# MN12832JC-TeensyLC.net
KiCad netlist of a schematic drawn in EAGLE
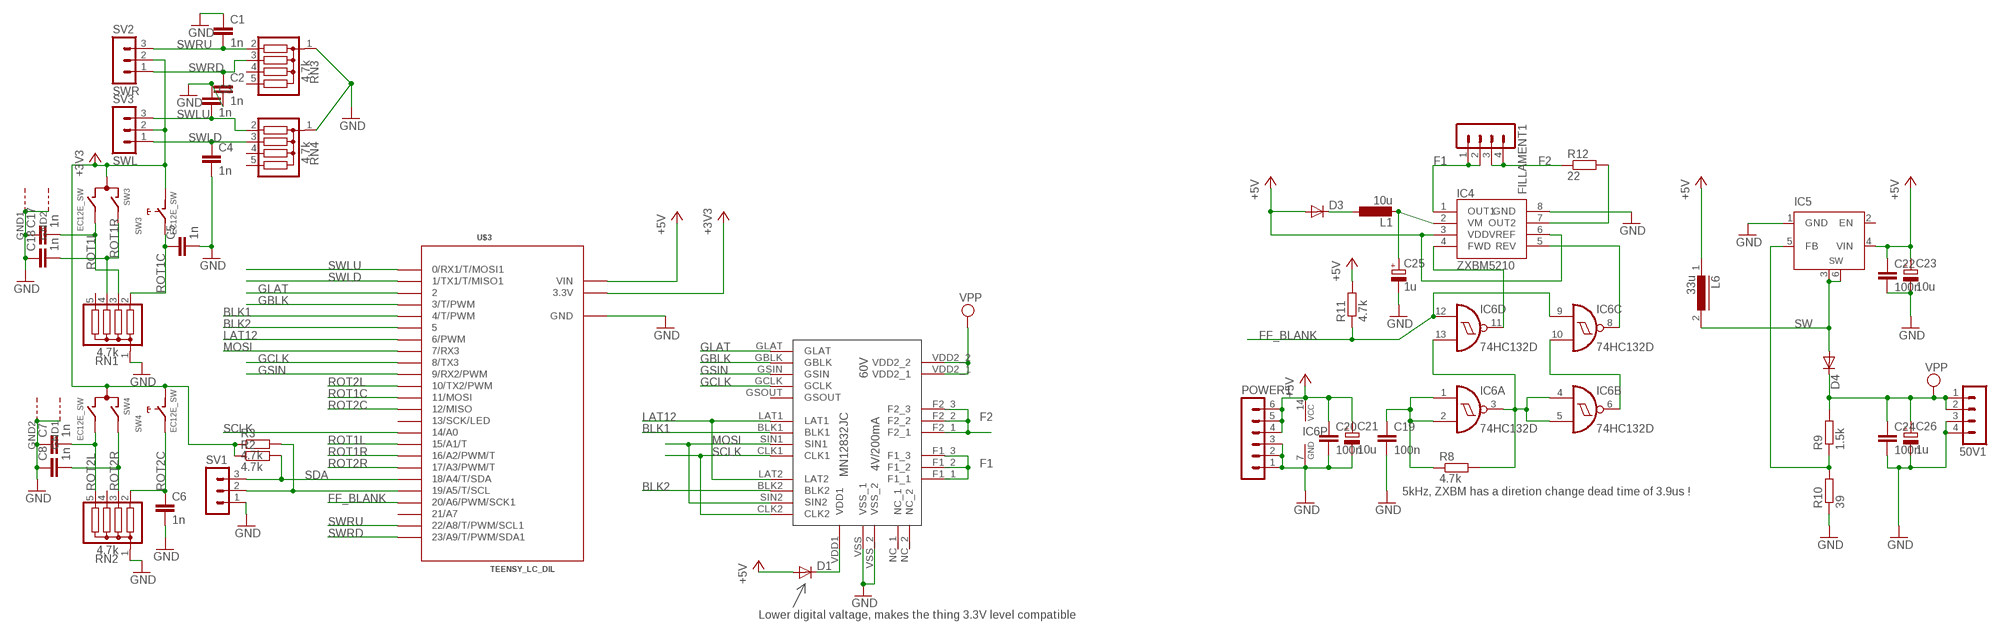
[diagram p0: schematic, sheet 1]

(export (version "E")
  (design (tool "Eeschema 10.0.6"))
  (components
    (comp (ref "50V1")
      (value "MA04-1")
      (footprint "eagle-import:MA04-1")
      (libsource (lib "eagle-import") (part "MA04-1"))
    )
    (comp (ref "C1")
      (value "1n")
      (footprint "eagle-import:C1206")
      (libsource (lib "eagle-import") (part "C-EUC1206"))
    )
    (comp (ref "C2")
      (value "1n")
      (footprint "eagle-import:C1206")
      (libsource (lib "eagle-import") (part "C-EUC1206"))
    )
    (comp (ref "C3")
      (value "1n")
      (footprint "eagle-import:C1206")
      (libsource (lib "eagle-import") (part "C-EUC1206"))
    )
    (comp (ref "C4")
      (value "1n")
      (footprint "eagle-import:C1206")
      (libsource (lib "eagle-import") (part "C-EUC1206"))
    )
    (comp (ref "C5")
      (value "1n")
      (footprint "eagle-import:C1206")
      (libsource (lib "eagle-import") (part "C-EUC1206"))
    )
    (comp (ref "C6")
      (value "1n")
      (footprint "eagle-import:C1206")
      (libsource (lib "eagle-import") (part "C-EUC1206"))
    )
    (comp (ref "C7")
      (value "1n")
      (footprint "eagle-import:C1206")
      (libsource (lib "eagle-import") (part "C-EUC1206"))
    )
    (comp (ref "C8")
      (value "1n")
      (footprint "eagle-import:C1206")
      (libsource (lib "eagle-import") (part "C-EUC1206"))
    )
    (comp (ref "C17")
      (value "1n")
      (footprint "eagle-import:C1206")
      (libsource (lib "eagle-import") (part "C-EUC1206"))
    )
    (comp (ref "C18")
      (value "1n")
      (footprint "eagle-import:C1206")
      (libsource (lib "eagle-import") (part "C-EUC1206"))
    )
    (comp (ref "C19")
      (value "100n")
      (footprint "eagle-import:C1206")
      (libsource (lib "eagle-import") (part "C-EUC1206"))
    )
    (comp (ref "C20")
      (value "100n")
      (footprint "eagle-import:C1206")
      (libsource (lib "eagle-import") (part "C-EUC1206"))
    )
    (comp (ref "C21")
      (value "10u")
      (footprint "eagle-import:153CLV-0807")
      (libsource (lib "eagle-import") (part "CPOL-EU153CLV-0807"))
    )
    (comp (ref "C22")
      (value "100n")
      (footprint "eagle-import:C1206")
      (libsource (lib "eagle-import") (part "C-EUC1206"))
    )
    (comp (ref "C23")
      (value "10u")
      (footprint "eagle-import:153CLV-0807")
      (libsource (lib "eagle-import") (part "CPOL-EU153CLV-0807"))
    )
    (comp (ref "C24")
      (value "100n")
      (footprint "eagle-import:C1206")
      (libsource (lib "eagle-import") (part "C-EUC1206"))
    )
    (comp (ref "C25")
      (value "1u")
      (footprint "eagle-import:153CLV-0505")
      (libsource (lib "eagle-import") (part "CPOL-EU153CLV-0505"))
    )
    (comp (ref "C26")
      (value "1u")
      (footprint "eagle-import:153CLV-0505")
      (libsource (lib "eagle-import") (part "CPOL-EU153CLV-0505"))
    )
    (comp (ref "D1")
      (value "DIODE-SMB")
      (footprint "eagle-import:SMB")
      (libsource (lib "eagle-import") (part "DIODE-SMB"))
    )
    (comp (ref "D3")
      (value "DIODE-SMB")
      (footprint "eagle-import:SMB")
      (libsource (lib "eagle-import") (part "DIODE-SMB"))
    )
    (comp (ref "D4")
      (value "DIODE-SMB")
      (footprint "eagle-import:SMB")
      (libsource (lib "eagle-import") (part "DIODE-SMB"))
    )
    (comp (ref "FILLAMENT1")
      (value "MA04-1")
      (footprint "eagle-import:MA04-1")
      (libsource (lib "eagle-import") (part "MA04-1"))
    )
    (comp (ref "IC4")
      (value "ZXBM5210")
      (footprint "eagle-import:SO8")
      (libsource (lib "eagle-import") (part "ZXBM5210"))
    )
    (comp (ref "IC5")
      (value "XL6009")
      (footprint "eagle-import:TO263-5")
      (libsource (lib "eagle-import") (part "XL6009"))
    )
    (comp (ref "IC6")
      (value "74HC132D")
      (footprint "eagle-import:SO14")
      (libsource (lib "eagle-import") (part "74132DHC"))
    )
    (comp (ref "L1")
      (value "10u")
      (footprint "eagle-import:L1812")
      (libsource (lib "eagle-import") (part "L-EUL1812"))
    )
    (comp (ref "L6")
      (value "33u")
      (footprint "eagle-import:DR125")
      (libsource (lib "eagle-import") (part "DR125"))
    )
    (comp (ref "POWER1")
      (value "MA06-1")
      (footprint "eagle-import:MA06-1")
      (libsource (lib "eagle-import") (part "MA06-1"))
    )
    (comp (ref "R2")
      (value "4.7k")
      (footprint "eagle-import:R1206")
      (libsource (lib "eagle-import") (part "R-EU_R1206"))
    )
    (comp (ref "R3")
      (value "4.7k")
      (footprint "eagle-import:R1206")
      (libsource (lib "eagle-import") (part "R-EU_R1206"))
    )
    (comp (ref "R8")
      (value "4.7k")
      (footprint "eagle-import:R1206")
      (libsource (lib "eagle-import") (part "R-EU_R1206"))
    )
    (comp (ref "R9")
      (value "1.5k")
      (footprint "eagle-import:R1206")
      (libsource (lib "eagle-import") (part "R-EU_R1206"))
    )
    (comp (ref "R10")
      (value "39")
      (footprint "eagle-import:R1206")
      (libsource (lib "eagle-import") (part "R-EU_R1206"))
    )
    (comp (ref "R11")
      (value "4.7k")
      (footprint "eagle-import:R1206")
      (libsource (lib "eagle-import") (part "R-EU_R1206"))
    )
    (comp (ref "R12")
      (value "22")
      (footprint "eagle-import:0411_15")
      (libsource (lib "eagle-import") (part "R-EU_0411/15"))
    )
    (comp (ref "RN1")
      (value "4.7k")
      (footprint "eagle-import:SIL5")
      (libsource (lib "eagle-import") (part "G04R"))
    )
    (comp (ref "RN2")
      (value "4.7k")
      (footprint "eagle-import:SIL5")
      (libsource (lib "eagle-import") (part "G04R"))
    )
    (comp (ref "RN3")
      (value "4.7k")
      (footprint "eagle-import:SIL5")
      (libsource (lib "eagle-import") (part "G04R"))
    )
    (comp (ref "RN4")
      (value "4.7k")
      (footprint "eagle-import:SIL5")
      (libsource (lib "eagle-import") (part "G04R"))
    )
    (comp (ref "SV1")
      (value "MA03-1")
      (footprint "eagle-import:MA03-1")
      (libsource (lib "eagle-import") (part "MA03-1"))
    )
    (comp (ref "SV2")
      (value "SWR")
      (footprint "eagle-import:MA03-1")
      (libsource (lib "eagle-import") (part "MA03-1"))
    )
    (comp (ref "SV3")
      (value "SWL")
      (footprint "eagle-import:MA03-1")
      (libsource (lib "eagle-import") (part "MA03-1"))
    )
    (comp (ref "SW3")
      (value "EC12E_SW")
      (footprint "eagle-import:ALPS_EC12E_SW")
      (fields (field (name "MPN") "EC12E2424407"))
      (libsource (lib "eagle-import") (part "EC12E_SW"))
    )
    (comp (ref "SW4")
      (value "EC12E_SW")
      (footprint "eagle-import:ALPS_EC12E_SW")
      (fields (field (name "MPN") "EC12E2424407"))
      (libsource (lib "eagle-import") (part "EC12E_SW"))
    )
    (comp (ref "U$1")
      (value "MN12832JC")
      (footprint "eagle-import:MN12832JC")
      (libsource (lib "eagle-import") (part "MN12832JC"))
    )
    (comp (ref "U$3")
      (value "TEENSY_LC_DIL")
      (footprint "eagle-import:TEENSY_3.0-3.2&LC_DIL")
      (libsource (lib "eagle-import") (part "TEENSY_LC_DIL"))
    )
  )
  (nets
    (net (code "1") (name "+3V3") (class "Default")
      (node (ref "R2") (pin "1") (pinfunction "1_1") (pintype "passive"))
      (node (ref "R3") (pin "1") (pinfunction "1_1") (pintype "passive"))
      (node (ref "SV2") (pin "2") (pinfunction "2_2") (pintype "passive"))
      (node (ref "SV3") (pin "2") (pinfunction "2_2") (pintype "passive"))
      (node (ref "SW3") (pin "C") (pinfunction "C_C") (pintype "passive"))
      (node (ref "SW3") (pin "D") (pinfunction "1_D") (pintype "passive"))
      (node (ref "SW4") (pin "C") (pinfunction "C_C") (pintype "passive"))
      (node (ref "SW4") (pin "D") (pinfunction "1_D") (pintype "passive"))
      (node (ref "U$3") (pin "3.3V") (pinfunction "3.3V_3.3V") (pintype "power_in"))
    )
    (net (code "2") (name "+5V") (class "Default")
      (node (ref "C20") (pin "1") (pinfunction "1_1") (pintype "passive"))
      (node (ref "C21") (pin "+") (pinfunction "+_+") (pintype "passive"))
      (node (ref "C22") (pin "1") (pinfunction "1_1") (pintype "passive"))
      (node (ref "C23") (pin "+") (pinfunction "+_+") (pintype "passive"))
      (node (ref "D1") (pin "A") (pinfunction "A_A") (pintype "passive"))
      (node (ref "D3") (pin "A") (pinfunction "A_A") (pintype "passive"))
      (node (ref "IC4") (pin "3") (pinfunction "VDD_3") (pintype "bidirectional"))
      (node (ref "IC4") (pin "6") (pinfunction "VREF_6") (pintype "bidirectional"))
      (node (ref "IC5") (pin "4") (pinfunction "VIN_4") (pintype "input"))
      (node (ref "IC6") (pin "14") (pinfunction "VCC_14") (pintype "power_in"))
      (node (ref "L6") (pin "1") (pinfunction "1_1") (pintype "passive"))
      (node (ref "POWER1") (pin "4") (pinfunction "4_4") (pintype "passive"))
      (node (ref "POWER1") (pin "5") (pinfunction "5_5") (pintype "passive"))
      (node (ref "POWER1") (pin "6") (pinfunction "6_6") (pintype "passive"))
      (node (ref "R11") (pin "2") (pinfunction "2_2") (pintype "passive"))
      (node (ref "U$3") (pin "VIN") (pinfunction "VIN_VIN") (pintype "power_in"))
    )
    (net (code "3") (name "/BLK1") (class "Default")
      (node (ref "U$1") (pin "BLK1") (pinfunction "BLK1_BLK1") (pintype "bidirectional"))
      (node (ref "U$3") (pin "4") (pinfunction "4/T/PWM_4") (pintype "bidirectional"))
    )
    (net (code "4") (name "/BLK2") (class "Default")
      (node (ref "U$1") (pin "BLK2") (pinfunction "BLK2_BLK2") (pintype "bidirectional"))
      (node (ref "U$3") (pin "5") (pinfunction "5_5") (pintype "bidirectional"))
    )
    (net (code "5") (name "/F1") (class "Default")
      (node (ref "FILLAMENT1") (pin "1") (pinfunction "1_1") (pintype "passive"))
      (node (ref "FILLAMENT1") (pin "2") (pinfunction "2_2") (pintype "passive"))
      (node (ref "IC4") (pin "1") (pinfunction "OUT1_1") (pintype "bidirectional"))
      (node (ref "U$1") (pin "F1_1") (pinfunction "F1_1_F1_1") (pintype "bidirectional"))
      (node (ref "U$1") (pin "F1_2") (pinfunction "F1_2_F1_2") (pintype "bidirectional"))
      (node (ref "U$1") (pin "F1_3") (pinfunction "F1_3_F1_3") (pintype "bidirectional"))
    )
    (net (code "6") (name "/F2") (class "Default")
      (node (ref "FILLAMENT1") (pin "3") (pinfunction "3_3") (pintype "passive"))
      (node (ref "FILLAMENT1") (pin "4") (pinfunction "4_4") (pintype "passive"))
      (node (ref "R12") (pin "1") (pinfunction "1_1") (pintype "passive"))
      (node (ref "U$1") (pin "F2_1") (pinfunction "F2_1_F2_1") (pintype "bidirectional"))
      (node (ref "U$1") (pin "F2_2") (pinfunction "F2_2_F2_2") (pintype "bidirectional"))
      (node (ref "U$1") (pin "F2_3") (pinfunction "F2_3_F2_3") (pintype "bidirectional"))
    )
    (net (code "7") (name "/FF_BLANK") (class "Default")
      (node (ref "IC6") (pin "12") (pinfunction "I0_12") (pintype "input"))
      (node (ref "IC6") (pin "9") (pinfunction "I0_9") (pintype "input"))
      (node (ref "R11") (pin "1") (pinfunction "1_1") (pintype "passive"))
      (node (ref "U$3") (pin "20/A6") (pinfunction "20/A6/PWM/SCK1_20/A6") (pintype "bidirectional"))
    )
    (net (code "8") (name "/GBLK") (class "Default")
      (node (ref "U$1") (pin "GBLK") (pinfunction "GBLK_GBLK") (pintype "bidirectional"))
      (node (ref "U$3") (pin "3") (pinfunction "3/T/PWM_3") (pintype "bidirectional"))
    )
    (net (code "9") (name "/GCLK") (class "Default")
      (node (ref "U$1") (pin "GCLK") (pinfunction "GCLK_GCLK") (pintype "bidirectional"))
      (node (ref "U$3") (pin "8") (pinfunction "8/TX3_8") (pintype "bidirectional"))
    )
    (net (code "10") (name "/GLAT") (class "Default")
      (node (ref "U$1") (pin "GLAT") (pinfunction "GLAT_GLAT") (pintype "bidirectional"))
      (node (ref "U$3") (pin "2") (pinfunction "2_2") (pintype "bidirectional"))
    )
    (net (code "11") (name "/GSIN") (class "Default")
      (node (ref "U$1") (pin "GSIN") (pinfunction "GSIN_GSIN") (pintype "bidirectional"))
      (node (ref "U$3") (pin "9") (pinfunction "9/RX2/PWM_9") (pintype "bidirectional"))
    )
    (net (code "12") (name "/LAT12") (class "Default")
      (node (ref "U$1") (pin "LAT1") (pinfunction "LAT1_LAT1") (pintype "bidirectional"))
      (node (ref "U$1") (pin "LAT2") (pinfunction "LAT2_LAT2") (pintype "bidirectional"))
      (node (ref "U$3") (pin "6") (pinfunction "6/PWM_6") (pintype "bidirectional"))
    )
    (net (code "13") (name "/MOSI") (class "Default")
      (node (ref "U$1") (pin "SIN1") (pinfunction "SIN1_SIN1") (pintype "bidirectional"))
      (node (ref "U$1") (pin "SIN2") (pinfunction "SIN2_SIN2") (pintype "bidirectional"))
      (node (ref "U$3") (pin "7") (pinfunction "7/RX3_7") (pintype "bidirectional"))
    )
    (net (code "14") (name "/ROT1C") (class "Default")
      (node (ref "C5") (pin "1") (pinfunction "1_1") (pintype "passive"))
      (node (ref "RN1") (pin "2") (pinfunction "2_2") (pintype "passive"))
      (node (ref "SW3") (pin "E") (pinfunction "2_E") (pintype "passive"))
      (node (ref "U$3") (pin "11") (pinfunction "11/MOSI_11") (pintype "bidirectional"))
    )
    (net (code "15") (name "/ROT1L") (class "Default")
      (node (ref "C17") (pin "2") (pinfunction "2_2") (pintype "passive"))
      (node (ref "RN1") (pin "3") (pinfunction "3_3") (pintype "passive"))
      (node (ref "SW3") (pin "B") (pinfunction "B_B") (pintype "passive"))
      (node (ref "U$3") (pin "15/A1") (pinfunction "15/A1/T_15/A1") (pintype "bidirectional"))
    )
    (net (code "16") (name "/ROT1R") (class "Default")
      (node (ref "C18") (pin "2") (pinfunction "2_2") (pintype "passive"))
      (node (ref "RN1") (pin "4") (pinfunction "4_4") (pintype "passive"))
      (node (ref "SW3") (pin "A") (pinfunction "A_A") (pintype "passive"))
      (node (ref "U$3") (pin "16/A2") (pinfunction "16/A2/PWM/T_16/A2") (pintype "bidirectional"))
    )
    (net (code "17") (name "/ROT2C") (class "Default")
      (node (ref "C6") (pin "1") (pinfunction "1_1") (pintype "passive"))
      (node (ref "RN2") (pin "2") (pinfunction "2_2") (pintype "passive"))
      (node (ref "SW4") (pin "E") (pinfunction "2_E") (pintype "passive"))
      (node (ref "U$3") (pin "12") (pinfunction "12/MISO_12") (pintype "bidirectional"))
    )
    (net (code "18") (name "/ROT2L") (class "Default")
      (node (ref "C7") (pin "2") (pinfunction "2_2") (pintype "passive"))
      (node (ref "RN2") (pin "5") (pinfunction "5_5") (pintype "passive"))
      (node (ref "SW4") (pin "B") (pinfunction "B_B") (pintype "passive"))
      (node (ref "U$3") (pin "10") (pinfunction "10/TX2/PWM_10") (pintype "bidirectional"))
    )
    (net (code "19") (name "/ROT2R") (class "Default")
      (node (ref "C8") (pin "2") (pinfunction "2_2") (pintype "passive"))
      (node (ref "RN2") (pin "3") (pinfunction "3_3") (pintype "passive"))
      (node (ref "SW4") (pin "A") (pinfunction "A_A") (pintype "passive"))
      (node (ref "U$3") (pin "17/A3") (pinfunction "17/A3/PWM/T_17/A3") (pintype "bidirectional"))
    )
    (net (code "20") (name "/SCLK") (class "Default")
      (node (ref "U$1") (pin "CLK1") (pinfunction "CLK1_CLK1") (pintype "bidirectional"))
      (node (ref "U$1") (pin "CLK2") (pinfunction "CLK2_CLK2") (pintype "bidirectional"))
      (node (ref "U$3") (pin "14/A0") (pinfunction "14/A0_14/A0") (pintype "bidirectional"))
    )
    (net (code "21") (name "/SDA") (class "Default")
      (node (ref "R2") (pin "2") (pinfunction "2_2") (pintype "passive"))
      (node (ref "SV1") (pin "3") (pinfunction "3_3") (pintype "passive"))
      (node (ref "U$3") (pin "18/A4") (pinfunction "18/A4/T/SDA_18/A4") (pintype "bidirectional"))
    )
    (net (code "22") (name "/SW") (class "Default")
      (node (ref "D4") (pin "A") (pinfunction "A_A") (pintype "passive"))
      (node (ref "IC5") (pin "3") (pinfunction "SW_3") (pintype "power_in"))
      (node (ref "IC5") (pin "6") (pinfunction "SW_6") (pintype "power_in"))
      (node (ref "L6") (pin "2") (pinfunction "2_2") (pintype "passive"))
    )
    (net (code "23") (name "/SWLD") (class "Default")
      (node (ref "C4") (pin "1") (pinfunction "1_1") (pintype "passive"))
      (node (ref "RN4") (pin "3") (pinfunction "3_3") (pintype "passive"))
      (node (ref "SV3") (pin "1") (pinfunction "1_1") (pintype "passive"))
      (node (ref "U$3") (pin "1") (pinfunction "1/TX1/T/MISO1_1") (pintype "bidirectional"))
    )
    (net (code "24") (name "/SWLU") (class "Default")
      (node (ref "C3") (pin "2") (pinfunction "2_2") (pintype "passive"))
      (node (ref "RN4") (pin "2") (pinfunction "2_2") (pintype "passive"))
      (node (ref "SV3") (pin "3") (pinfunction "3_3") (pintype "passive"))
      (node (ref "U$3") (pin "0") (pinfunction "0/RX1/T/MOSI1_0") (pintype "bidirectional"))
    )
    (net (code "25") (name "/SWRD") (class "Default")
      (node (ref "C2") (pin "1") (pinfunction "1_1") (pintype "passive"))
      (node (ref "RN3") (pin "3") (pinfunction "3_3") (pintype "passive"))
      (node (ref "SV2") (pin "1") (pinfunction "1_1") (pintype "passive"))
      (node (ref "U$3") (pin "23/A9") (pinfunction "23/A9/T/PWM/SDA1_23/A9") (pintype "bidirectional"))
    )
    (net (code "26") (name "/SWRU") (class "Default")
      (node (ref "C1") (pin "2") (pinfunction "2_2") (pintype "passive"))
      (node (ref "RN3") (pin "2") (pinfunction "2_2") (pintype "passive"))
      (node (ref "SV2") (pin "3") (pinfunction "3_3") (pintype "passive"))
      (node (ref "U$3") (pin "22/A8") (pinfunction "22/A8/T/PWM/SCL1_22/A8") (pintype "bidirectional"))
    )
    (net (code "27") (name "GND") (class "Default")
      (node (ref "50V1") (pin "3") (pinfunction "3_3") (pintype "passive"))
      (node (ref "50V1") (pin "4") (pinfunction "4_4") (pintype "passive"))
      (node (ref "C1") (pin "1") (pinfunction "1_1") (pintype "passive"))
      (node (ref "C17") (pin "1") (pinfunction "1_1") (pintype "passive"))
      (node (ref "C18") (pin "1") (pinfunction "1_1") (pintype "passive"))
      (node (ref "C19") (pin "2") (pinfunction "2_2") (pintype "passive"))
      (node (ref "C2") (pin "2") (pinfunction "2_2") (pintype "passive"))
      (node (ref "C20") (pin "2") (pinfunction "2_2") (pintype "passive"))
      (node (ref "C21") (pin "-") (pinfunction "-_-") (pintype "passive"))
      (node (ref "C22") (pin "2") (pinfunction "2_2") (pintype "passive"))
      (node (ref "C23") (pin "-") (pinfunction "-_-") (pintype "passive"))
      (node (ref "C24") (pin "2") (pinfunction "2_2") (pintype "passive"))
      (node (ref "C25") (pin "-") (pinfunction "-_-") (pintype "passive"))
      (node (ref "C26") (pin "-") (pinfunction "-_-") (pintype "passive"))
      (node (ref "C3") (pin "1") (pinfunction "1_1") (pintype "passive"))
      (node (ref "C4") (pin "2") (pinfunction "2_2") (pintype "passive"))
      (node (ref "C5") (pin "2") (pinfunction "2_2") (pintype "passive"))
      (node (ref "C6") (pin "2") (pinfunction "2_2") (pintype "passive"))
      (node (ref "C7") (pin "1") (pinfunction "1_1") (pintype "passive"))
      (node (ref "C8") (pin "1") (pinfunction "1_1") (pintype "passive"))
      (node (ref "IC4") (pin "8") (pinfunction "GND_8") (pintype "bidirectional"))
      (node (ref "IC5") (pin "1") (pinfunction "GND_1") (pintype "input"))
      (node (ref "IC6") (pin "7") (pinfunction "GND_7") (pintype "power_in"))
      (node (ref "POWER1") (pin "1") (pinfunction "1_1") (pintype "passive"))
      (node (ref "POWER1") (pin "2") (pinfunction "2_2") (pintype "passive"))
      (node (ref "POWER1") (pin "3") (pinfunction "3_3") (pintype "passive"))
      (node (ref "R10") (pin "1") (pinfunction "1_1") (pintype "passive"))
      (node (ref "RN1") (pin "1") (pinfunction "1_1") (pintype "passive"))
      (node (ref "RN2") (pin "1") (pinfunction "1_1") (pintype "passive"))
      (node (ref "RN3") (pin "1") (pinfunction "1_1") (pintype "passive"))
      (node (ref "RN4") (pin "1") (pinfunction "1_1") (pintype "passive"))
      (node (ref "SV1") (pin "1") (pinfunction "1_1") (pintype "passive"))
      (node (ref "SW3") (pin "GND1") (pinfunction "G_GND1") (pintype "passive"))
      (node (ref "SW3") (pin "GND2") (pinfunction "G_GND2") (pintype "passive"))
      (node (ref "SW4") (pin "GND1") (pinfunction "G_GND1") (pintype "passive"))
      (node (ref "SW4") (pin "GND2") (pinfunction "G_GND2") (pintype "passive"))
      (node (ref "U$1") (pin "VSS") (pinfunction "VSS_1_VSS") (pintype "bidirectional"))
      (node (ref "U$1") (pin "VSS_2") (pinfunction "VSS_2_VSS_2") (pintype "bidirectional"))
      (node (ref "U$3") (pin "AGND") (pinfunction "GND_AGND") (pintype "power_in"))
      (node (ref "U$3") (pin "GND") (pinfunction "GND_GND") (pintype "power_in"))
    )
    (net (code "28") (name "Net-(D1-PadC)") (class "Default")
      (node (ref "D1") (pin "C") (pinfunction "C_C") (pintype "passive"))
      (node (ref "U$1") (pin "VDD1") (pinfunction "VDD1_VDD1") (pintype "bidirectional"))
    )
    (net (code "29") (name "Net-(D3-PadC)") (class "Default")
      (node (ref "D3") (pin "C") (pinfunction "C_C") (pintype "passive"))
      (node (ref "L1") (pin "1") (pinfunction "1_1") (pintype "passive"))
    )
    (net (code "30") (name "Net-(IC4-FWD)") (class "Default")
      (node (ref "IC4") (pin "4") (pinfunction "FWD_4") (pintype "bidirectional"))
      (node (ref "IC6") (pin "11") (pinfunction "O_11") (pintype "output"))
    )
    (net (code "31") (name "Net-(IC4-OUT2)") (class "Default")
      (node (ref "IC4") (pin "7") (pinfunction "OUT2_7") (pintype "bidirectional"))
      (node (ref "R12") (pin "2") (pinfunction "2_2") (pintype "passive"))
    )
    (net (code "32") (name "Net-(IC4-REV)") (class "Default")
      (node (ref "IC4") (pin "5") (pinfunction "REV_5") (pintype "bidirectional"))
      (node (ref "IC6") (pin "8") (pinfunction "O_8") (pintype "output"))
    )
    (net (code "33") (name "Net-(IC4-VM)") (class "Default")
      (node (ref "C25") (pin "+") (pinfunction "+_+") (pintype "passive"))
      (node (ref "IC4") (pin "2") (pinfunction "VM_2") (pintype "bidirectional"))
      (node (ref "L1") (pin "2") (pinfunction "2_2") (pintype "passive"))
    )
    (net (code "34") (name "Net-(IC5-FB)") (class "Default")
      (node (ref "IC5") (pin "5") (pinfunction "FB_5") (pintype "input"))
      (node (ref "R10") (pin "2") (pinfunction "2_2") (pintype "passive"))
      (node (ref "R9") (pin "1") (pinfunction "1_1") (pintype "passive"))
    )
    (net (code "35") (name "Net-(IC6A-I0)") (class "Default")
      (node (ref "C19") (pin "1") (pinfunction "1_1") (pintype "passive"))
      (node (ref "IC6") (pin "1") (pinfunction "I0_1") (pintype "input"))
      (node (ref "IC6") (pin "2") (pinfunction "I1_2") (pintype "input"))
      (node (ref "R8") (pin "1") (pinfunction "1_1") (pintype "passive"))
    )
    (net (code "36") (name "Net-(IC6A-O)") (class "Default")
      (node (ref "IC6") (pin "13") (pinfunction "I1_13") (pintype "input"))
      (node (ref "IC6") (pin "3") (pinfunction "O_3") (pintype "output"))
      (node (ref "IC6") (pin "4") (pinfunction "I0_4") (pintype "input"))
      (node (ref "IC6") (pin "5") (pinfunction "I1_5") (pintype "input"))
      (node (ref "R8") (pin "2") (pinfunction "2_2") (pintype "passive"))
    )
    (net (code "37") (name "Net-(IC6B-O)") (class "Default")
      (node (ref "IC6") (pin "10") (pinfunction "I1_10") (pintype "input"))
      (node (ref "IC6") (pin "6") (pinfunction "O_6") (pintype "output"))
    )
    (net (code "38") (name "Net-(U$3-19{slash}A5{slash}T{slash}SCL)") (class "Default")
      (node (ref "R3") (pin "2") (pinfunction "2_2") (pintype "passive"))
      (node (ref "SV1") (pin "2") (pinfunction "2_2") (pintype "passive"))
      (node (ref "U$3") (pin "19/A5") (pinfunction "19/A5/T/SCL_19/A5") (pintype "bidirectional"))
    )
    (net (code "39") (name "VPP") (class "Default")
      (node (ref "50V1") (pin "1") (pinfunction "1_1") (pintype "passive"))
      (node (ref "50V1") (pin "2") (pinfunction "2_2") (pintype "passive"))
      (node (ref "C24") (pin "1") (pinfunction "1_1") (pintype "passive"))
      (node (ref "C26") (pin "+") (pinfunction "+_+") (pintype "passive"))
      (node (ref "D4") (pin "C") (pinfunction "C_C") (pintype "passive"))
      (node (ref "R9") (pin "2") (pinfunction "2_2") (pintype "passive"))
      (node (ref "U$1") (pin "VDD2_1") (pinfunction "VDD2_1_VDD2_1") (pintype "bidirectional"))
      (node (ref "U$1") (pin "VDD2_2") (pinfunction "VDD2_2_VDD2_2") (pintype "bidirectional"))
    )
    (net (code "40") (name "unconnected-(IC5-EN-Pad2)") (class "Default")
      (node (ref "IC5") (pin "2") (pinfunction "EN_2") (pintype "output"))
    )
    (net (code "41") (name "unconnected-(RN1-Pad5)") (class "Default")
      (node (ref "RN1") (pin "5") (pinfunction "5_5") (pintype "passive"))
    )
    (net (code "42") (name "unconnected-(RN2-Pad4)") (class "Default")
      (node (ref "RN2") (pin "4") (pinfunction "4_4") (pintype "passive"))
    )
    (net (code "43") (name "unconnected-(RN3-Pad4)") (class "Default")
      (node (ref "RN3") (pin "4") (pinfunction "4_4") (pintype "passive"))
    )
    (net (code "44") (name "unconnected-(RN3-Pad5)") (class "Default")
      (node (ref "RN3") (pin "5") (pinfunction "5_5") (pintype "passive"))
    )
    (net (code "45") (name "unconnected-(RN4-Pad4)") (class "Default")
      (node (ref "RN4") (pin "4") (pinfunction "4_4") (pintype "passive"))
    )
    (net (code "46") (name "unconnected-(RN4-Pad5)") (class "Default")
      (node (ref "RN4") (pin "5") (pinfunction "5_5") (pintype "passive"))
    )
    (net (code "47") (name "unconnected-(U$1-PadGSOUT)") (class "Default")
      (node (ref "U$1") (pin "GSOUT") (pinfunction "GSOUT_GSOUT") (pintype "bidirectional"))
    )
    (net (code "48") (name "unconnected-(U$1-PadNC_1)") (class "Default")
      (node (ref "U$1") (pin "NC_1") (pinfunction "NC_1_NC_1") (pintype "bidirectional"))
    )
    (net (code "49") (name "unconnected-(U$1-PadNC_2)") (class "Default")
      (node (ref "U$1") (pin "NC_2") (pinfunction "NC_2_NC_2") (pintype "bidirectional"))
    )
    (net (code "50") (name "unconnected-(U$3-13{slash}SCK{slash}LED-Pad13)") (class "Default")
      (node (ref "U$3") (pin "13") (pinfunction "13/SCK/LED_13") (pintype "bidirectional"))
    )
    (net (code "51") (name "unconnected-(U$3-Pad21{slash}A7)") (class "Default")
      (node (ref "U$3") (pin "21/A7") (pinfunction "21/A7_21/A7") (pintype "bidirectional"))
    )
  )
)
